# Sheet1.net
KiCad netlist of a schematic drawn in Altium Designer
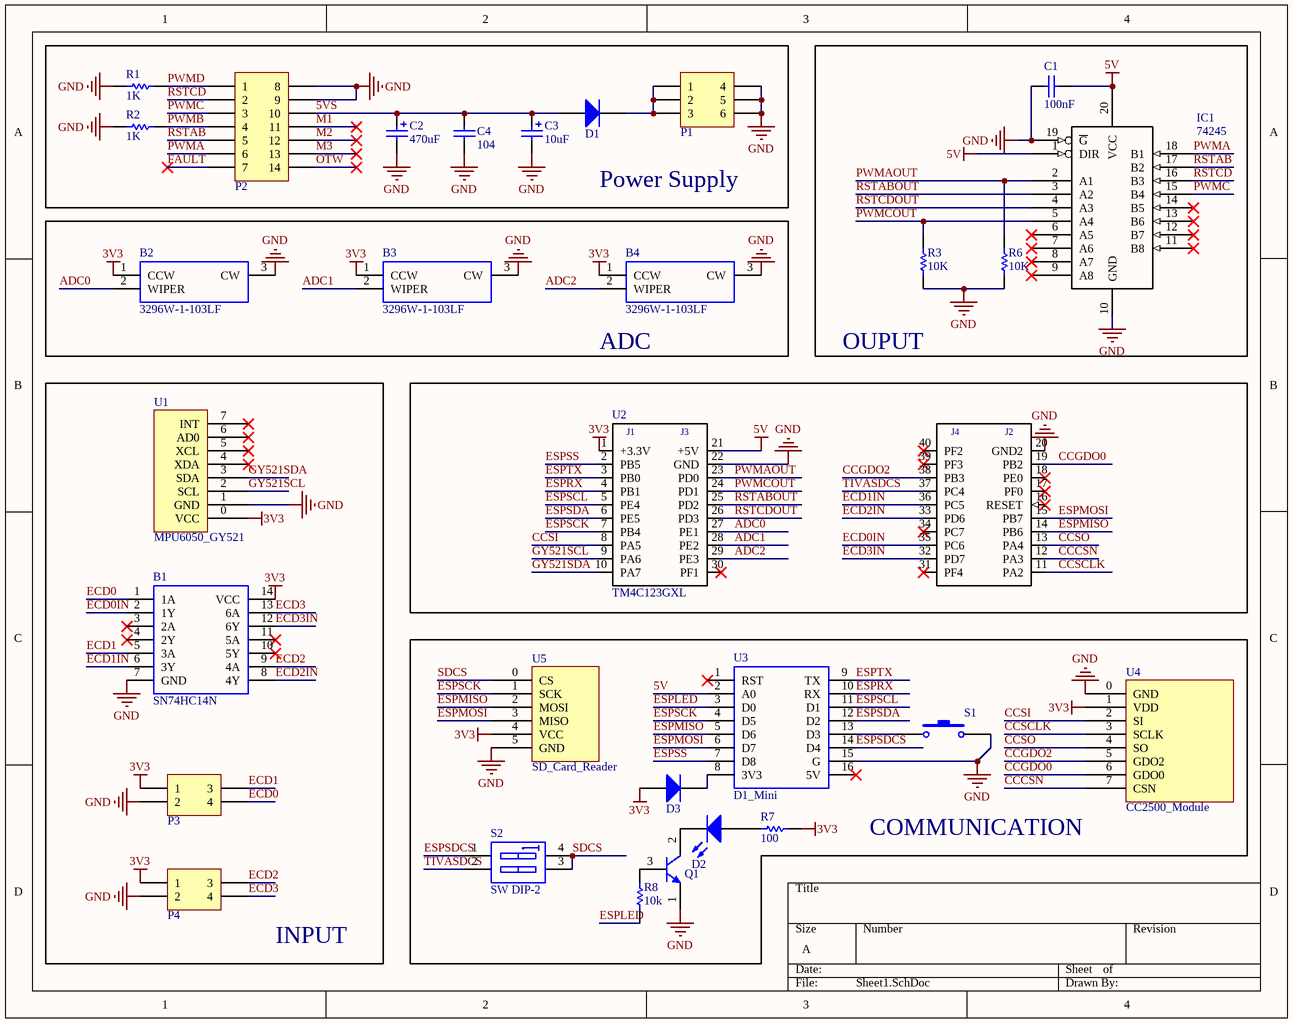
[diagram p0: Sheet1.SchDoc]

(export (version "E")
  (design (tool "Eeschema 10.0.6"))
  (components
    (comp (ref "B1")
      (value "SN74HC14N")
      (footprint "DIP254P762X508-14")
      (description "Hex invertor,SN74HC14N DIP14 2-6V 25pcs")
      (fields (field (name "RS PART NUMBER") "0442943"))
      (libsource (lib "SN74HC14N") (part "SN74HC14N"))
    )
    (comp (ref "B2")
      (value "3296W-1-103LF")
      (footprint "SHDR3W54P0X254_1X3_953X483X1155P")
      (fields (field (name "RS PART NUMBER") "5219647P"))
      (libsource (lib "3296W-1-103LF") (part "3296W-1-103LF"))
    )
    (comp (ref "B3")
      (value "3296W-1-103LF")
      (footprint "SHDR3W54P0X254_1X3_953X483X1155P")
      (fields (field (name "RS PART NUMBER") "5219647P"))
      (libsource (lib "3296W-1-103LF") (part "3296W-1-103LF"))
    )
    (comp (ref "B4")
      (value "3296W-1-103LF")
      (footprint "SHDR3W54P0X254_1X3_953X483X1155P")
      (fields (field (name "RS PART NUMBER") "5219647P"))
      (libsource (lib "3296W-1-103LF") (part "3296W-1-103LF"))
    )
    (comp (ref "C1")
      (value "100nF")
      (footprint "CN1")
      (description "Capacitor")
      (fields (field (name "Comment") "Cap Non-Pol"))
      (libsource (lib "PIF_Library") (part "Cap Non-Pol"))
    )
    (comp (ref "C2")
      (value "470uF")
      (footprint "CP1/2")
      (description "Polarized Capacitor (Radial)")
      (fields (field (name "Comment") "Cap Pol"))
      (libsource (lib "PIF_Library") (part "Cap Pol"))
    )
    (comp (ref "C3")
      (value "10uF")
      (footprint "CP1/2")
      (description "Polarized Capacitor (Radial)")
      (fields (field (name "Comment") "Cap Pol"))
      (libsource (lib "PIF_Library") (part "Cap Pol"))
    )
    (comp (ref "C4")
      (value "104")
      (footprint "CN1")
      (description "Capacitor")
      (fields (field (name "Comment") "Cap Non-Pol"))
      (libsource (lib "PIF_Library") (part "Cap Non-Pol"))
    )
    (comp (ref "D1")
      (value "Diode")
      (footprint "D1A")
      (description "Default Diode")
      (libsource (lib "PIF_Library") (part "Diode"))
    )
    (comp (ref "D2") (value "LED") (footprint "LED-3mm") (libsource (lib "PIF_Library") (part "LED")))
    (comp (ref "D3")
      (value "Diode")
      (footprint "D1A")
      (description "Default Diode")
      (libsource (lib "PIF_Library") (part "Diode"))
    )
    (comp (ref "IC1")
      (value "74245")
      (footprint "DIP20")
      (description "Octal bus tranceiver; 3-state")
      (fields (field (name "COPYRIGHT BY") "VanDungEvn@gmail.com"))
      (libsource (lib "My Library") (part "74245_1"))
    )
    (comp (ref "P1")
      (value "Header 3X2")
      (footprint "JP3x2")
      (description "Header, 3-Pin, Dual row")
      (fields (field (name "PUBLISHER") "Altium Limited"))
      (libsource (lib "PIF_Library") (part "Header 3X2"))
    )
    (comp (ref "P2")
      (value "Header 7X2")
      (footprint "JP7X2")
      (description "Header, 7-Pin, Dual row")
      (fields (field (name "PUBLISHER") "Altium Limited"))
      (libsource (lib "PIF_Library") (part "Header 7X2"))
    )
    (comp (ref "P3")
      (value "Header 2X2")
      (footprint "JP2X2")
      (description "Header, 2-Pin, Dual row")
      (fields (field (name "PUBLISHER") "Altium Limited"))
      (libsource (lib "PIF_Library") (part "Header 2X2"))
    )
    (comp (ref "P4")
      (value "Header 2X2")
      (footprint "JP2X2")
      (description "Header, 2-Pin, Dual row")
      (fields (field (name "PUBLISHER") "Altium Limited"))
      (libsource (lib "PIF_Library") (part "Header 2X2"))
    )
    (comp (ref "Q1")
      (value "C1815")
      (footprint "QTO-92")
      (description "NPN Bipolar Transistor")
      (libsource (lib "PIF_Library") (part "C1815"))
    )
    (comp (ref "R1")
      (value "1K")
      (footprint "RES 1/2W")
      (description "Resistor")
      (fields (field (name "Comment") "RESISTOR"))
      (libsource (lib "PIF_Library") (part "RESISTOR"))
    )
    (comp (ref "R2")
      (value "1K")
      (footprint "RES 1/2W")
      (description "Resistor")
      (fields (field (name "Comment") "RESISTOR"))
      (libsource (lib "PIF_Library") (part "RESISTOR"))
    )
    (comp (ref "R3")
      (value "10K")
      (footprint "RES 1/2W")
      (description "Resistor")
      (fields (field (name "Comment") "RESISTOR"))
      (libsource (lib "PIF_Library") (part "RESISTOR"))
    )
    (comp (ref "R6")
      (value "10K")
      (footprint "RES 1/2W")
      (description "Resistor")
      (fields (field (name "Comment") "RESISTOR"))
      (libsource (lib "PIF_Library") (part "RESISTOR"))
    )
    (comp (ref "R7")
      (value "100")
      (footprint "RES 1/2W")
      (description "Resistor")
      (fields (field (name "Comment") "RESISTOR"))
      (libsource (lib "PIF_Library") (part "RESISTOR"))
    )
    (comp (ref "R8")
      (value "10k")
      (footprint "RES 1/2W")
      (description "Resistor")
      (fields (field (name "Comment") "RESISTOR"))
      (libsource (lib "PIF_Library") (part "RESISTOR"))
    )
    (comp (ref "S1")
      (value "Tact SW - 2Pin")
      (footprint "SW2")
      (description "Switch button 2 pin")
      (libsource (lib "PIF_Library") (part "Tact SW - 2Pin"))
    )
    (comp (ref "S2")
      (value "SW DIP-2")
      (footprint "DIPSWITCH2")
      (description "DIP Switch, 2 Position, SPST")
      (fields (field (name "PUBLISHER") "Altium Limited"))
      (libsource (lib "My Library") (part "SW DIP-2"))
    )
    (comp (ref "U1")
      (value "MPU6050_GY521")
      (footprint "MPU6050_GY521")
      (libsource (lib "AltiumLib") (part "MPU6050_GY521"))
    )
    (comp (ref "U2")
      (value "TM4C123GXL")
      (footprint "EK-TM4C123GXL")
      (libsource (lib "AltiumLib") (part "EK-TM4C123GXL"))
    )
    (comp (ref "U3") (value "D1_Mini") (footprint "D1_Mini") (libsource (lib "AltiumLib") (part "D1_Mini")))
    (comp (ref "U4")
      (value "CC2500_Module")
      (footprint "CC2500_module")
      (libsource (lib "AltiumLib") (part "CC2500_Module"))
    )
    (comp (ref "U5")
      (value "SD_Card_Reader")
      (footprint "SD_Card_Reader")
      (libsource (lib "AltiumLib") (part "SD_Card_Reader"))
    )
  )
  (nets
    (net (code "1") (name "/5VS") (class "Default")
      (node (ref "C2") (pin "1") (pinfunction "1_1") (pintype "passive"))
      (node (ref "C3") (pin "1") (pinfunction "1_1") (pintype "passive"))
      (node (ref "C4") (pin "1") (pinfunction "1_1") (pintype "passive"))
      (node (ref "D1") (pin "1") (pinfunction "A_1") (pintype "passive"))
      (node (ref "P2") (pin "10") (pinfunction "10_10") (pintype "passive"))
    )
    (net (code "2") (name "/ADC0") (class "Default")
      (node (ref "B2") (pin "2") (pinfunction "WIPER_2") (pintype "passive"))
      (node (ref "U2") (pin "27") (pinfunction "PE1_27") (pintype "bidirectional"))
    )
    (net (code "3") (name "/ADC1") (class "Default")
      (node (ref "B3") (pin "2") (pinfunction "WIPER_2") (pintype "passive"))
      (node (ref "U2") (pin "28") (pinfunction "PE2_28") (pintype "bidirectional"))
    )
    (net (code "4") (name "/ADC2") (class "Default")
      (node (ref "B4") (pin "2") (pinfunction "WIPER_2") (pintype "passive"))
      (node (ref "U2") (pin "29") (pinfunction "PE3_29") (pintype "bidirectional"))
    )
    (net (code "5") (name "/CCCSN") (class "Default")
      (node (ref "U2") (pin "12") (pinfunction "PA3_12") (pintype "bidirectional"))
      (node (ref "U4") (pin "7") (pinfunction "CSN_7") (pintype "passive"))
    )
    (net (code "6") (name "/CCGDO0") (class "Default")
      (node (ref "U2") (pin "19") (pinfunction "PB2_19") (pintype "bidirectional"))
      (node (ref "U4") (pin "6") (pinfunction "GDO0_6") (pintype "passive"))
    )
    (net (code "7") (name "/CCGDO2") (class "Default")
      (node (ref "U2") (pin "38") (pinfunction "PB3_38") (pintype "bidirectional"))
      (node (ref "U4") (pin "5") (pinfunction "GDO2_5") (pintype "passive"))
    )
    (net (code "8") (name "/CCSCLK") (class "Default")
      (node (ref "U2") (pin "11") (pinfunction "PA2_11") (pintype "bidirectional"))
      (node (ref "U4") (pin "3") (pinfunction "SCLK_3") (pintype "passive"))
    )
    (net (code "9") (name "/CCSI") (class "Default")
      (node (ref "U2") (pin "8") (pinfunction "PA5_8") (pintype "bidirectional"))
      (node (ref "U4") (pin "2") (pinfunction "SI_2") (pintype "passive"))
    )
    (net (code "10") (name "/CCSO") (class "Default")
      (node (ref "U2") (pin "13") (pinfunction "PA4_13") (pintype "bidirectional"))
      (node (ref "U4") (pin "4") (pinfunction "SO_4") (pintype "passive"))
    )
    (net (code "11") (name "/ECD0") (class "Default")
      (node (ref "B1") (pin "1") (pinfunction "1A_1") (pintype "passive"))
      (node (ref "P3") (pin "4") (pinfunction "4_4") (pintype "passive"))
    )
    (net (code "12") (name "/ECD0IN") (class "Default")
      (node (ref "B1") (pin "2") (pinfunction "1Y_2") (pintype "passive"))
      (node (ref "U2") (pin "35") (pinfunction "PC6_35") (pintype "bidirectional"))
    )
    (net (code "13") (name "/ECD1") (class "Default")
      (node (ref "B1") (pin "5") (pinfunction "3A_5") (pintype "passive"))
      (node (ref "P3") (pin "3") (pinfunction "3_3") (pintype "passive"))
    )
    (net (code "14") (name "/ECD1IN") (class "Default")
      (node (ref "B1") (pin "6") (pinfunction "3Y_6") (pintype "passive"))
      (node (ref "U2") (pin "36") (pinfunction "PC5_36") (pintype "bidirectional"))
    )
    (net (code "15") (name "/ECD2") (class "Default")
      (node (ref "B1") (pin "9") (pinfunction "4A_9") (pintype "passive"))
      (node (ref "P4") (pin "3") (pinfunction "3_3") (pintype "passive"))
    )
    (net (code "16") (name "/ECD2IN") (class "Default")
      (node (ref "B1") (pin "8") (pinfunction "4Y_8") (pintype "passive"))
      (node (ref "U2") (pin "33") (pinfunction "PD6_33") (pintype "bidirectional"))
    )
    (net (code "17") (name "/ECD3") (class "Default")
      (node (ref "B1") (pin "13") (pinfunction "6A_13") (pintype "passive"))
      (node (ref "P4") (pin "4") (pinfunction "4_4") (pintype "passive"))
    )
    (net (code "18") (name "/ECD3IN") (class "Default")
      (node (ref "B1") (pin "12") (pinfunction "6Y_12") (pintype "passive"))
      (node (ref "U2") (pin "32") (pinfunction "PD7_32") (pintype "bidirectional"))
    )
    (net (code "19") (name "/ESPLED") (class "Default")
      (node (ref "R8") (pin "1") (pinfunction "1_1") (pintype "passive"))
      (node (ref "U3") (pin "3") (pinfunction "D0_3") (pintype "passive"))
    )
    (net (code "20") (name "/ESPMISO") (class "Default")
      (node (ref "U2") (pin "14") (pinfunction "PB6_14") (pintype "bidirectional"))
      (node (ref "U3") (pin "5") (pinfunction "D6_5") (pintype "passive"))
      (node (ref "U5") (pin "2") (pinfunction "MOSI_2") (pintype "passive"))
    )
    (net (code "21") (name "/ESPMOSI") (class "Default")
      (node (ref "U2") (pin "15") (pinfunction "PB7_15") (pintype "bidirectional"))
      (node (ref "U3") (pin "6") (pinfunction "D7_6") (pintype "passive"))
      (node (ref "U5") (pin "3") (pinfunction "MISO_3") (pintype "passive"))
    )
    (net (code "22") (name "/ESPRX") (class "Default")
      (node (ref "U2") (pin "4") (pinfunction "PB1_4") (pintype "bidirectional"))
      (node (ref "U3") (pin "10") (pinfunction "RX_10") (pintype "passive"))
    )
    (net (code "23") (name "/ESPSCK") (class "Default")
      (node (ref "U2") (pin "7") (pinfunction "PB4_7") (pintype "bidirectional"))
      (node (ref "U3") (pin "4") (pinfunction "D5_4") (pintype "passive"))
      (node (ref "U5") (pin "1") (pinfunction "SCK_1") (pintype "passive"))
    )
    (net (code "24") (name "/ESPSCL") (class "Default")
      (node (ref "U2") (pin "5") (pinfunction "PE4_5") (pintype "bidirectional"))
      (node (ref "U3") (pin "11") (pinfunction "D1_11") (pintype "passive"))
    )
    (net (code "25") (name "/ESPSDA") (class "Default")
      (node (ref "U2") (pin "6") (pinfunction "PE5_6") (pintype "bidirectional"))
      (node (ref "U3") (pin "12") (pinfunction "D2_12") (pintype "passive"))
    )
    (net (code "26") (name "/ESPSDCS") (class "Default")
      (node (ref "S2") (pin "1") (pinfunction "A1_1") (pintype "passive"))
      (node (ref "U3") (pin "14") (pinfunction "D4_14") (pintype "passive"))
    )
    (net (code "27") (name "/ESPSS") (class "Default")
      (node (ref "U2") (pin "2") (pinfunction "PB5_2") (pintype "bidirectional"))
      (node (ref "U3") (pin "7") (pinfunction "D8_7") (pintype "passive"))
    )
    (net (code "28") (name "/ESPTX") (class "Default")
      (node (ref "U2") (pin "3") (pinfunction "PB0_3") (pintype "bidirectional"))
      (node (ref "U3") (pin "9") (pinfunction "TX_9") (pintype "passive"))
    )
    (net (code "29") (name "/FAULT") (class "Default")
      (node (ref "P2") (pin "7") (pinfunction "7_7") (pintype "passive+no_connect"))
    )
    (net (code "30") (name "/GY521SCL") (class "Default")
      (node (ref "U1") (pin "2") (pinfunction "SCL_2") (pintype "passive"))
      (node (ref "U2") (pin "9") (pinfunction "PA6_9") (pintype "bidirectional"))
    )
    (net (code "31") (name "/GY521SDA") (class "Default")
      (node (ref "U1") (pin "3") (pinfunction "SDA_3") (pintype "passive"))
      (node (ref "U2") (pin "10") (pinfunction "PA7_10") (pintype "bidirectional"))
    )
    (net (code "32") (name "/M1") (class "Default")
      (node (ref "P2") (pin "11") (pinfunction "11_11") (pintype "passive+no_connect"))
    )
    (net (code "33") (name "/M2") (class "Default")
      (node (ref "P2") (pin "12") (pinfunction "12_12") (pintype "passive+no_connect"))
    )
    (net (code "34") (name "/M3") (class "Default")
      (node (ref "P2") (pin "13") (pinfunction "13_13") (pintype "passive+no_connect"))
    )
    (net (code "35") (name "/OTW") (class "Default")
      (node (ref "P2") (pin "14") (pinfunction "14_14") (pintype "passive+no_connect"))
    )
    (net (code "36") (name "/PWMA") (class "Default")
      (node (ref "IC1") (pin "18") (pinfunction "B1_18") (pintype "input"))
      (node (ref "P2") (pin "6") (pinfunction "6_6") (pintype "passive"))
    )
    (net (code "37") (name "/PWMAOUT") (class "Default")
      (node (ref "IC1") (pin "2") (pinfunction "A1_2") (pintype "tri_state"))
      (node (ref "R6") (pin "2") (pinfunction "2_2") (pintype "passive"))
      (node (ref "U2") (pin "23") (pinfunction "PD0_23") (pintype "bidirectional"))
    )
    (net (code "38") (name "/PWMB") (class "Default")
      (node (ref "P2") (pin "4") (pinfunction "4_4") (pintype "passive"))
      (node (ref "R2") (pin "2") (pinfunction "2_2") (pintype "passive"))
    )
    (net (code "39") (name "/PWMC") (class "Default")
      (node (ref "IC1") (pin "15") (pinfunction "B4_15") (pintype "input"))
      (node (ref "P2") (pin "3") (pinfunction "3_3") (pintype "passive"))
    )
    (net (code "40") (name "/PWMCOUT") (class "Default")
      (node (ref "IC1") (pin "5") (pinfunction "A4_5") (pintype "tri_state"))
      (node (ref "R3") (pin "2") (pinfunction "2_2") (pintype "passive"))
      (node (ref "U2") (pin "24") (pinfunction "PD1_24") (pintype "bidirectional"))
    )
    (net (code "41") (name "/PWMD") (class "Default")
      (node (ref "P2") (pin "1") (pinfunction "1_1") (pintype "passive"))
      (node (ref "R1") (pin "2") (pinfunction "2_2") (pintype "passive"))
    )
    (net (code "42") (name "/RSTAB") (class "Default")
      (node (ref "IC1") (pin "17") (pinfunction "B2_17") (pintype "input"))
      (node (ref "P2") (pin "5") (pinfunction "5_5") (pintype "passive"))
    )
    (net (code "43") (name "/RSTABOUT") (class "Default")
      (node (ref "IC1") (pin "3") (pinfunction "A2_3") (pintype "tri_state"))
      (node (ref "U2") (pin "25") (pinfunction "PD2_25") (pintype "bidirectional"))
    )
    (net (code "44") (name "/RSTCD") (class "Default")
      (node (ref "IC1") (pin "16") (pinfunction "B3_16") (pintype "input"))
      (node (ref "P2") (pin "2") (pinfunction "2_2") (pintype "passive"))
    )
    (net (code "45") (name "/RSTCDOUT") (class "Default")
      (node (ref "IC1") (pin "4") (pinfunction "A3_4") (pintype "tri_state"))
      (node (ref "U2") (pin "26") (pinfunction "PD3_26") (pintype "bidirectional"))
    )
    (net (code "46") (name "/SDCS") (class "Default")
      (node (ref "S2") (pin "3") (pinfunction "B2_3") (pintype "passive"))
      (node (ref "S2") (pin "4") (pinfunction "B1_4") (pintype "passive"))
      (node (ref "U5") (pin "0") (pinfunction "CS_0") (pintype "passive"))
    )
    (net (code "47") (name "/TIVASDCS") (class "Default")
      (node (ref "S2") (pin "2") (pinfunction "A2_2") (pintype "passive"))
      (node (ref "U2") (pin "37") (pinfunction "PC4_37") (pintype "bidirectional"))
    )
    (net (code "48") (name "3V3") (class "Default")
      (node (ref "B1") (pin "14") (pinfunction "VCC_14") (pintype "passive"))
      (node (ref "B2") (pin "1") (pinfunction "CCW_1") (pintype "passive"))
      (node (ref "B3") (pin "1") (pinfunction "CCW_1") (pintype "passive"))
      (node (ref "B4") (pin "1") (pinfunction "CCW_1") (pintype "passive"))
      (node (ref "D3") (pin "1") (pinfunction "A_1") (pintype "passive"))
      (node (ref "P3") (pin "1") (pinfunction "1_1") (pintype "passive"))
      (node (ref "P4") (pin "1") (pinfunction "1_1") (pintype "passive"))
      (node (ref "R7") (pin "2") (pinfunction "2_2") (pintype "passive"))
      (node (ref "U1") (pin "0") (pinfunction "VCC_0") (pintype "power_in"))
      (node (ref "U2") (pin "1") (pinfunction "+3.3V_1") (pintype "power_in"))
      (node (ref "U4") (pin "1") (pinfunction "VDD_1") (pintype "passive"))
      (node (ref "U5") (pin "4") (pinfunction "VCC_4") (pintype "power_in"))
    )
    (net (code "49") (name "5V") (class "Default")
      (node (ref "C1") (pin "2") (pinfunction "2_2") (pintype "passive"))
      (node (ref "IC1") (pin "1") (pinfunction "DIR_1") (pintype "input"))
      (node (ref "IC1") (pin "20") (pinfunction "VCC_20") (pintype "power_in"))
      (node (ref "U2") (pin "21") (pinfunction "+5V_21") (pintype "power_in"))
      (node (ref "U3") (pin "2") (pinfunction "A0_2") (pintype "passive"))
    )
    (net (code "50") (name "GND") (class "Default")
      (node (ref "B1") (pin "7") (pinfunction "GND_7") (pintype "passive"))
      (node (ref "B2") (pin "3") (pinfunction "CW_3") (pintype "passive"))
      (node (ref "B3") (pin "3") (pinfunction "CW_3") (pintype "passive"))
      (node (ref "B4") (pin "3") (pinfunction "CW_3") (pintype "passive"))
      (node (ref "C1") (pin "1") (pinfunction "1_1") (pintype "passive"))
      (node (ref "C2") (pin "2") (pinfunction "2_2") (pintype "passive"))
      (node (ref "C3") (pin "2") (pinfunction "2_2") (pintype "passive"))
      (node (ref "C4") (pin "2") (pinfunction "2_2") (pintype "passive"))
      (node (ref "IC1") (pin "10") (pinfunction "GND_10") (pintype "power_in"))
      (node (ref "IC1") (pin "19") (pinfunction "~{G}_19") (pintype "input"))
      (node (ref "P1") (pin "4") (pinfunction "4_4") (pintype "passive"))
      (node (ref "P1") (pin "5") (pinfunction "5_5") (pintype "passive"))
      (node (ref "P1") (pin "6") (pinfunction "6_6") (pintype "passive"))
      (node (ref "P2") (pin "8") (pinfunction "8_8") (pintype "passive"))
      (node (ref "P2") (pin "9") (pinfunction "9_9") (pintype "passive"))
      (node (ref "P3") (pin "2") (pinfunction "2_2") (pintype "passive"))
      (node (ref "P4") (pin "2") (pinfunction "2_2") (pintype "passive"))
      (node (ref "Q1") (pin "1") (pinfunction "E_1") (pintype "passive"))
      (node (ref "R1") (pin "1") (pinfunction "1_1") (pintype "passive"))
      (node (ref "R2") (pin "1") (pinfunction "1_1") (pintype "passive"))
      (node (ref "R3") (pin "1") (pinfunction "1_1") (pintype "passive"))
      (node (ref "R6") (pin "1") (pinfunction "1_1") (pintype "passive"))
      (node (ref "S1") (pin "2") (pinfunction "2_2") (pintype "passive"))
      (node (ref "U1") (pin "1") (pinfunction "GND_1") (pintype "power_in"))
      (node (ref "U2") (pin "20") (pinfunction "GND2_20") (pintype "power_in"))
      (node (ref "U2") (pin "22") (pinfunction "GND_22") (pintype "power_in"))
      (node (ref "U3") (pin "15") (pinfunction "G_15") (pintype "passive"))
      (node (ref "U4") (pin "0") (pinfunction "GND_0") (pintype "power_in"))
      (node (ref "U5") (pin "5") (pinfunction "GND_5") (pintype "power_in"))
    )
    (net (code "51") (name "Net-(D1-K)") (class "Default")
      (node (ref "D1") (pin "2") (pinfunction "K_2") (pintype "passive"))
      (node (ref "P1") (pin "1") (pinfunction "1_1") (pintype "passive"))
      (node (ref "P1") (pin "2") (pinfunction "2_2") (pintype "passive"))
      (node (ref "P1") (pin "3") (pinfunction "3_3") (pintype "passive"))
    )
    (net (code "52") (name "Net-(D2-A)") (class "Default")
      (node (ref "D2") (pin "1") (pinfunction "A_1") (pintype "passive"))
      (node (ref "R7") (pin "1") (pinfunction "1_1") (pintype "passive"))
    )
    (net (code "53") (name "Net-(D2-K)") (class "Default")
      (node (ref "D2") (pin "2") (pinfunction "K_2") (pintype "passive"))
      (node (ref "Q1") (pin "2") (pinfunction "C_2") (pintype "passive"))
    )
    (net (code "54") (name "Net-(D3-K)") (class "Default")
      (node (ref "D3") (pin "2") (pinfunction "K_2") (pintype "passive"))
      (node (ref "U3") (pin "8") (pinfunction "3V3_8") (pintype "passive"))
    )
    (net (code "55") (name "Net-(Q1-B)") (class "Default")
      (node (ref "Q1") (pin "3") (pinfunction "B_3") (pintype "passive"))
      (node (ref "R8") (pin "2") (pinfunction "2_2") (pintype "passive"))
    )
    (net (code "56") (name "Net-(U3-D3)") (class "Default")
      (node (ref "S1") (pin "1") (pinfunction "1_1") (pintype "passive"))
      (node (ref "U3") (pin "13") (pinfunction "D3_13") (pintype "passive"))
    )
    (net (code "57") (name "unconnected-(B1-2A-Pad3)") (class "Default")
      (node (ref "B1") (pin "3") (pinfunction "2A_3") (pintype "passive+no_connect"))
    )
    (net (code "58") (name "unconnected-(B1-2Y-Pad4)") (class "Default")
      (node (ref "B1") (pin "4") (pinfunction "2Y_4") (pintype "passive+no_connect"))
    )
    (net (code "59") (name "unconnected-(B1-5A-Pad11)") (class "Default")
      (node (ref "B1") (pin "11") (pinfunction "5A_11") (pintype "passive+no_connect"))
    )
    (net (code "60") (name "unconnected-(B1-5Y-Pad10)") (class "Default")
      (node (ref "B1") (pin "10") (pinfunction "5Y_10") (pintype "passive+no_connect"))
    )
    (net (code "61") (name "unconnected-(IC1-A5-Pad6)") (class "Default")
      (node (ref "IC1") (pin "6") (pinfunction "A5_6") (pintype "tri_state+no_connect"))
    )
    (net (code "62") (name "unconnected-(IC1-A6-Pad7)") (class "Default")
      (node (ref "IC1") (pin "7") (pinfunction "A6_7") (pintype "tri_state+no_connect"))
    )
    (net (code "63") (name "unconnected-(IC1-A7-Pad8)") (class "Default")
      (node (ref "IC1") (pin "8") (pinfunction "A7_8") (pintype "tri_state+no_connect"))
    )
    (net (code "64") (name "unconnected-(IC1-A8-Pad9)") (class "Default")
      (node (ref "IC1") (pin "9") (pinfunction "A8_9") (pintype "tri_state+no_connect"))
    )
    (net (code "65") (name "unconnected-(IC1-B5-Pad14)") (class "Default")
      (node (ref "IC1") (pin "14") (pinfunction "B5_14") (pintype "input+no_connect"))
    )
    (net (code "66") (name "unconnected-(IC1-B6-Pad13)") (class "Default")
      (node (ref "IC1") (pin "13") (pinfunction "B6_13") (pintype "input+no_connect"))
    )
    (net (code "67") (name "unconnected-(IC1-B7-Pad12)") (class "Default")
      (node (ref "IC1") (pin "12") (pinfunction "B7_12") (pintype "input+no_connect"))
    )
    (net (code "68") (name "unconnected-(IC1-B8-Pad11)") (class "Default")
      (node (ref "IC1") (pin "11") (pinfunction "B8_11") (pintype "input+no_connect"))
    )
    (net (code "69") (name "unconnected-(U1-AD0-Pad6)") (class "Default")
      (node (ref "U1") (pin "6") (pinfunction "AD0_6") (pintype "passive+no_connect"))
    )
    (net (code "70") (name "unconnected-(U1-INT-Pad7)") (class "Default")
      (node (ref "U1") (pin "7") (pinfunction "INT_7") (pintype "passive+no_connect"))
    )
    (net (code "71") (name "unconnected-(U1-XCL-Pad5)") (class "Default")
      (node (ref "U1") (pin "5") (pinfunction "XCL_5") (pintype "passive+no_connect"))
    )
    (net (code "72") (name "unconnected-(U1-XDA-Pad4)") (class "Default")
      (node (ref "U1") (pin "4") (pinfunction "XDA_4") (pintype "passive+no_connect"))
    )
    (net (code "73") (name "unconnected-(U2-PC7-Pad34)") (class "Default")
      (node (ref "U2") (pin "34") (pinfunction "PC7_34") (pintype "bidirectional+no_connect"))
    )
    (net (code "74") (name "unconnected-(U2-PE0-Pad18)") (class "Default")
      (node (ref "U2") (pin "18") (pinfunction "PE0_18") (pintype "bidirectional+no_connect"))
    )
    (net (code "75") (name "unconnected-(U2-PF0-Pad17)") (class "Default")
      (node (ref "U2") (pin "17") (pinfunction "PF0_17") (pintype "bidirectional+no_connect"))
    )
    (net (code "76") (name "unconnected-(U2-PF1-Pad30)") (class "Default")
      (node (ref "U2") (pin "30") (pinfunction "PF1_30") (pintype "bidirectional+no_connect"))
    )
    (net (code "77") (name "unconnected-(U2-PF2-Pad40)") (class "Default")
      (node (ref "U2") (pin "40") (pinfunction "PF2_40") (pintype "bidirectional+no_connect"))
    )
    (net (code "78") (name "unconnected-(U2-PF3-Pad39)") (class "Default")
      (node (ref "U2") (pin "39") (pinfunction "PF3_39") (pintype "bidirectional+no_connect"))
    )
    (net (code "79") (name "unconnected-(U2-PF4-Pad31)") (class "Default")
      (node (ref "U2") (pin "31") (pinfunction "PF4_31") (pintype "bidirectional+no_connect"))
    )
    (net (code "80") (name "unconnected-(U2-RESET-Pad16)") (class "Default")
      (node (ref "U2") (pin "16") (pinfunction "RESET_16") (pintype "input+no_connect"))
    )
    (net (code "81") (name "unconnected-(U3-5V-Pad16)") (class "Default")
      (node (ref "U3") (pin "16") (pinfunction "5V_16") (pintype "passive+no_connect"))
    )
    (net (code "82") (name "unconnected-(U3-RST-Pad1)") (class "Default")
      (node (ref "U3") (pin "1") (pinfunction "RST_1") (pintype "passive+no_connect"))
    )
  )
)
